# MOSFET_IRF540.net
KiCad netlist of a schematic drawn in Altium Designer
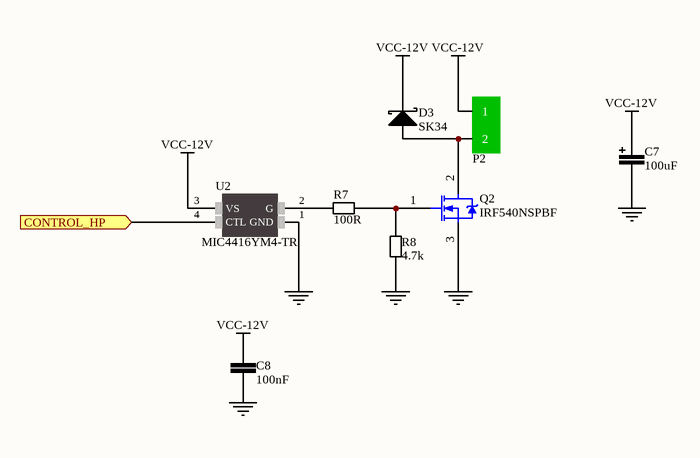
[diagram p0: MOSFET_IRF540.SchDoc]

(export (version "E")
  (design (tool "Eeschema 10.0.6"))
  (components
    (comp (ref "C7")
      (value "100uF")
      (footprint "CAP5X11_RADIAL")
      (description "CAP ALU 4.7u 25V 20%")
      (libsource (lib "Capacitors") (part "00004704"))
    )
    (comp (ref "C8")
      (value "100nF")
      (footprint "CER_0805")
      (description "CAP CER 100n 50V X7R 10% 0805")
      (libsource (lib "Capacitors") (part "00002105"))
    )
    (comp (ref "D3")
      (value "SK34")
      (footprint "DO214AC")
      (description "DIODE SCHOTTKY 40V 3A DO214AC")
      (fields (field (name "MANUFACTURER") "Vishay Semiconductor Diodes Division"))
      (libsource (lib "Discrete_Semiconductor") (part "SK34"))
    )
    (comp (ref "P2")
      (value "DRV_B3")
      (footprint "MOTOR_CON")
      (description "CONNECTOR FOR MOTOR OUTPUT")
      (libsource (lib "Electro_Mechanical") (part "MOT_CONN"))
    )
    (comp (ref "Q2")
      (value "IRF540NSPBF")
      (footprint "D2PAK-2")
      (description "N-MOS")
      (fields (field (name "MANUFACTURER") "INTERNATIONAL RECTIFIER"))
      (libsource (lib "Discrete_Semiconductor") (part "IRF540N"))
    )
    (comp (ref "R7")
      (value "100R")
      (footprint "RESC2013X38N-0805-NOOVERLAY")
      (description "RES SMD 100 Ohm 1/8W 0805")
      (fields (field (name "POWER") "0.125W, 1/8W"))
      (libsource (lib "Resistors") (part "00001000"))
    )
    (comp (ref "R8")
      (value "4.7k")
      (footprint "RESC2013X38N-0805-NOOVERLAY")
      (description "RES SMD 4.7 kOhm 1/8W 0805")
      (fields (field (name "POWER") "0.125W, 1/8W"))
      (libsource (lib "Resistors") (part "00004701"))
    )
    (comp (ref "U2")
      (value "MIC4416YM4-TR")
      (footprint "SOT143-4")
      (description "IC DRIVER MOSF LOW SIDE SOT143-4")
      (libsource (lib "Integrated_circuits") (part "MIC4416"))
    )
  )
  (nets
    (net (code "1") (name "/CONTROL_HP") (class "Default")
      (node (ref "U2") (pin "4") (pinfunction "CTL_4") (pintype "passive"))
    )
    (net (code "2") (name "GND") (class "Default")
      (node (ref "C7") (pin "2") (pinfunction "2_2") (pintype "passive"))
      (node (ref "C8") (pin "1") (pinfunction "1_1") (pintype "passive"))
      (node (ref "Q2") (pin "3") (pinfunction "S_3") (pintype "passive"))
      (node (ref "R8") (pin "1") (pinfunction "1_1") (pintype "passive"))
      (node (ref "U2") (pin "1") (pinfunction "GND_1") (pintype "passive"))
    )
    (net (code "3") (name "Net-(D3-Anode)") (class "Default")
      (node (ref "D3") (pin "2") (pinfunction "Anode_2") (pintype "passive"))
      (node (ref "P2") (pin "2") (pinfunction "2_2") (pintype "passive"))
      (node (ref "Q2") (pin "2") (pinfunction "D_2") (pintype "passive"))
    )
    (net (code "4") (name "Net-(Q2-G)") (class "Default")
      (node (ref "Q2") (pin "1") (pinfunction "G_1") (pintype "passive"))
      (node (ref "R7") (pin "2") (pinfunction "2_2") (pintype "passive"))
      (node (ref "R8") (pin "2") (pinfunction "2_2") (pintype "passive"))
    )
    (net (code "5") (name "Net-(U2-G)") (class "Default")
      (node (ref "R7") (pin "1") (pinfunction "1_1") (pintype "passive"))
      (node (ref "U2") (pin "2") (pinfunction "G_2") (pintype "passive"))
    )
    (net (code "6") (name "VCC-12V") (class "Default")
      (node (ref "C7") (pin "1") (pinfunction "1_1") (pintype "passive"))
      (node (ref "C8") (pin "2") (pinfunction "2_2") (pintype "passive"))
      (node (ref "D3") (pin "1") (pinfunction "Cathode_1") (pintype "passive"))
      (node (ref "P2") (pin "1") (pinfunction "1_1") (pintype "passive"))
      (node (ref "U2") (pin "3") (pinfunction "VS_3") (pintype "passive"))
    )
  )
)
